# Main.net
KiCad netlist of a schematic drawn in Altium Designer
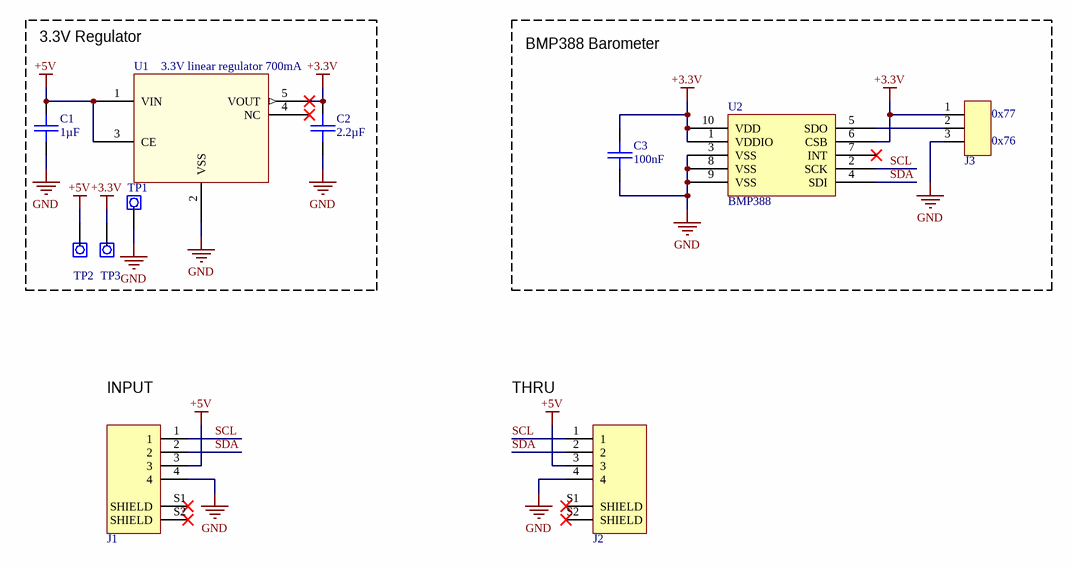
[diagram p0: Main.SchDoc]

(export (version "E")
  (design (tool "Eeschema 10.0.6"))
  (components
    (comp (ref "C1")
      (value "1µF")
      (footprint "0603_CAP")
      (libsource (lib "Moonlight_Components") (part "Capacitor"))
    )
    (comp (ref "C2")
      (value "2.2µF")
      (footprint "0603_CAP")
      (libsource (lib "Moonlight_Components") (part "Capacitor"))
    )
    (comp (ref "C3")
      (value "100nF")
      (footprint "0603_CAP")
      (libsource (lib "Moonlight_Components") (part "Capacitor"))
    )
    (comp (ref "J1")
      (value "4 pin vertical JST GH")
      (footprint "JST_BM04B-GHS-TBT(LF)(SN)(N)")
      (description "JST GH vertical 4 pin\r\nDigiKey part no. 455-1580-1-ND")
      (fields (field (name "MF") "JST Sales") (field (name "DIGI-KEY_PART_NUMBER") "455-1580-1-ND"))
      (libsource (lib "") (part "BM04B-GHS-TBT(LF)(SN)(N)_1"))
    )
    (comp (ref "J2")
      (value "4 pin vertical JST GH")
      (footprint "JST_BM04B-GHS-TBT(LF)(SN)(N)")
      (description "JST GH vertical 4 pin\r\nDigiKey part no. 455-1580-1-ND")
      (fields (field (name "MF") "JST Sales") (field (name "DIGI-KEY_PART_NUMBER") "455-1580-1-ND"))
      (libsource (lib "Moonlight_Components") (part "BM04B-GHS-TBT(LF)(SN)(N)"))
    )
    (comp (ref "J3")
      (value "Generic 3 pin 100 mil header")
      (footprint "HEADER-3-POS_100_mil")
      (libsource (lib "Moonlight_Components") (part "3 pin 100 mil header"))
    )
    (comp (ref "TP1") (value "GND") (footprint "Testpoint2") (libsource (lib "") (part "Testpoint_1")))
    (comp (ref "TP2")
      (value "5V")
      (footprint "Testpoint2")
      (libsource (lib "Moonlight_Components") (part "Testpoint"))
    )
    (comp (ref "TP3")
      (value "3.3V")
      (footprint "Testpoint2")
      (libsource (lib "Moonlight_Components") (part "Testpoint"))
    )
    (comp (ref "U1")
      (value "3.3V linear regulator 700mA")
      (footprint "SOT-25_TOR")
      (description "Digikey part no. 893-1143-1-ND")
      (fields
        (field (name "MANUFACTURER_PART_NUMBER") "XC6222B331MR-G")
        (field (name "COPYRIGHT") "Copyright (C) 2018 Accelerated Designs. All rights reserved")
      )
      (libsource (lib "Moonlight_Components") (part "XC6222B331MR-G"))
    )
    (comp (ref "U2")
      (value "BMP388")
      (footprint "QFN_BMP388_BOS")
      (description "No Description Available")
      (fields (field (name "COPYRIGHT") "Copyright (C) 2018 Accelerated Designs. All rights reserved"))
      (libsource (lib "Moonlight_Components") (part "BMP388"))
    )
  )
  (nets
    (net (code "1") (name "+3.3V") (class "Default")
      (node (ref "C2") (pin "1") (pinfunction "1_1") (pintype "passive"))
      (node (ref "C3") (pin "1") (pinfunction "1_1") (pintype "passive"))
      (node (ref "J3") (pin "1") (pinfunction "*_1") (pintype "passive"))
      (node (ref "TP3") (pin "1") (pinfunction "1_1") (pintype "passive"))
      (node (ref "U1") (pin "5") (pinfunction "VOUT_5") (pintype "output"))
      (node (ref "U2") (pin "1") (pinfunction "VDDIO_1") (pintype "power_in"))
      (node (ref "U2") (pin "10") (pinfunction "VDD_10") (pintype "power_in"))
      (node (ref "U2") (pin "6") (pinfunction "CSB_6") (pintype "passive"))
    )
    (net (code "2") (name "+5V") (class "Default")
      (node (ref "C1") (pin "1") (pinfunction "1_1") (pintype "passive"))
      (node (ref "J1") (pin "3") (pinfunction "3_3") (pintype "passive"))
      (node (ref "J2") (pin "3") (pinfunction "3_3") (pintype "passive"))
      (node (ref "TP2") (pin "1") (pinfunction "1_1") (pintype "passive"))
      (node (ref "U1") (pin "1") (pinfunction "VIN_1") (pintype "power_in"))
      (node (ref "U1") (pin "3") (pinfunction "CE_3") (pintype "passive"))
    )
    (net (code "3") (name "/SCL") (class "Default")
      (node (ref "J1") (pin "1") (pinfunction "1_1") (pintype "passive"))
      (node (ref "J2") (pin "1") (pinfunction "1_1") (pintype "passive"))
      (node (ref "U2") (pin "2") (pinfunction "SCK_2") (pintype "passive"))
    )
    (net (code "4") (name "/SDA") (class "Default")
      (node (ref "J1") (pin "2") (pinfunction "2_2") (pintype "passive"))
      (node (ref "J2") (pin "2") (pinfunction "2_2") (pintype "passive"))
      (node (ref "U2") (pin "4") (pinfunction "SDI_4") (pintype "passive"))
    )
    (net (code "5") (name "GND") (class "Default")
      (node (ref "C1") (pin "2") (pinfunction "2_2") (pintype "passive"))
      (node (ref "C2") (pin "2") (pinfunction "2_2") (pintype "passive"))
      (node (ref "C3") (pin "2") (pinfunction "2_2") (pintype "passive"))
      (node (ref "J1") (pin "4") (pinfunction "4_4") (pintype "passive"))
      (node (ref "J2") (pin "4") (pinfunction "4_4") (pintype "passive"))
      (node (ref "J3") (pin "3") (pinfunction "*_3") (pintype "passive"))
      (node (ref "TP1") (pin "1") (pinfunction "1_1") (pintype "passive"))
      (node (ref "U1") (pin "2") (pinfunction "VSS_2") (pintype "passive"))
      (node (ref "U2") (pin "3") (pinfunction "VSS_3") (pintype "passive"))
      (node (ref "U2") (pin "8") (pinfunction "VSS_8") (pintype "passive"))
      (node (ref "U2") (pin "9") (pinfunction "VSS_9") (pintype "passive"))
    )
    (net (code "6") (name "Net-(U2-SDO)") (class "Default")
      (node (ref "J3") (pin "2") (pinfunction "*_2") (pintype "passive"))
      (node (ref "U2") (pin "5") (pinfunction "SDO_5") (pintype "passive"))
    )
    (net (code "7") (name "unconnected-(J1-SHIELD-PadS1)") (class "Default")
      (node (ref "J1") (pin "S1") (pinfunction "SHIELD_S1") (pintype "passive+no_connect"))
    )
    (net (code "8") (name "unconnected-(J1-SHIELD-PadS2)") (class "Default")
      (node (ref "J1") (pin "S2") (pinfunction "SHIELD_S2") (pintype "passive+no_connect"))
    )
    (net (code "9") (name "unconnected-(J2-SHIELD-PadS1)") (class "Default")
      (node (ref "J2") (pin "S1") (pinfunction "SHIELD_S1") (pintype "passive+no_connect"))
    )
    (net (code "10") (name "unconnected-(J2-SHIELD-PadS2)") (class "Default")
      (node (ref "J2") (pin "S2") (pinfunction "SHIELD_S2") (pintype "passive+no_connect"))
    )
    (net (code "11") (name "unconnected-(U1-NC-Pad4)") (class "Default")
      (node (ref "U1") (pin "4") (pinfunction "NC_4") (pintype "passive+no_connect"))
    )
    (net (code "12") (name "unconnected-(U2-INT-Pad7)") (class "Default")
      (node (ref "U2") (pin "7") (pinfunction "INT_7") (pintype "passive+no_connect"))
    )
  )
)
